# pca10095_sheet3_interface_mcu.net
KiCad netlist of a schematic drawn in Altium Designer
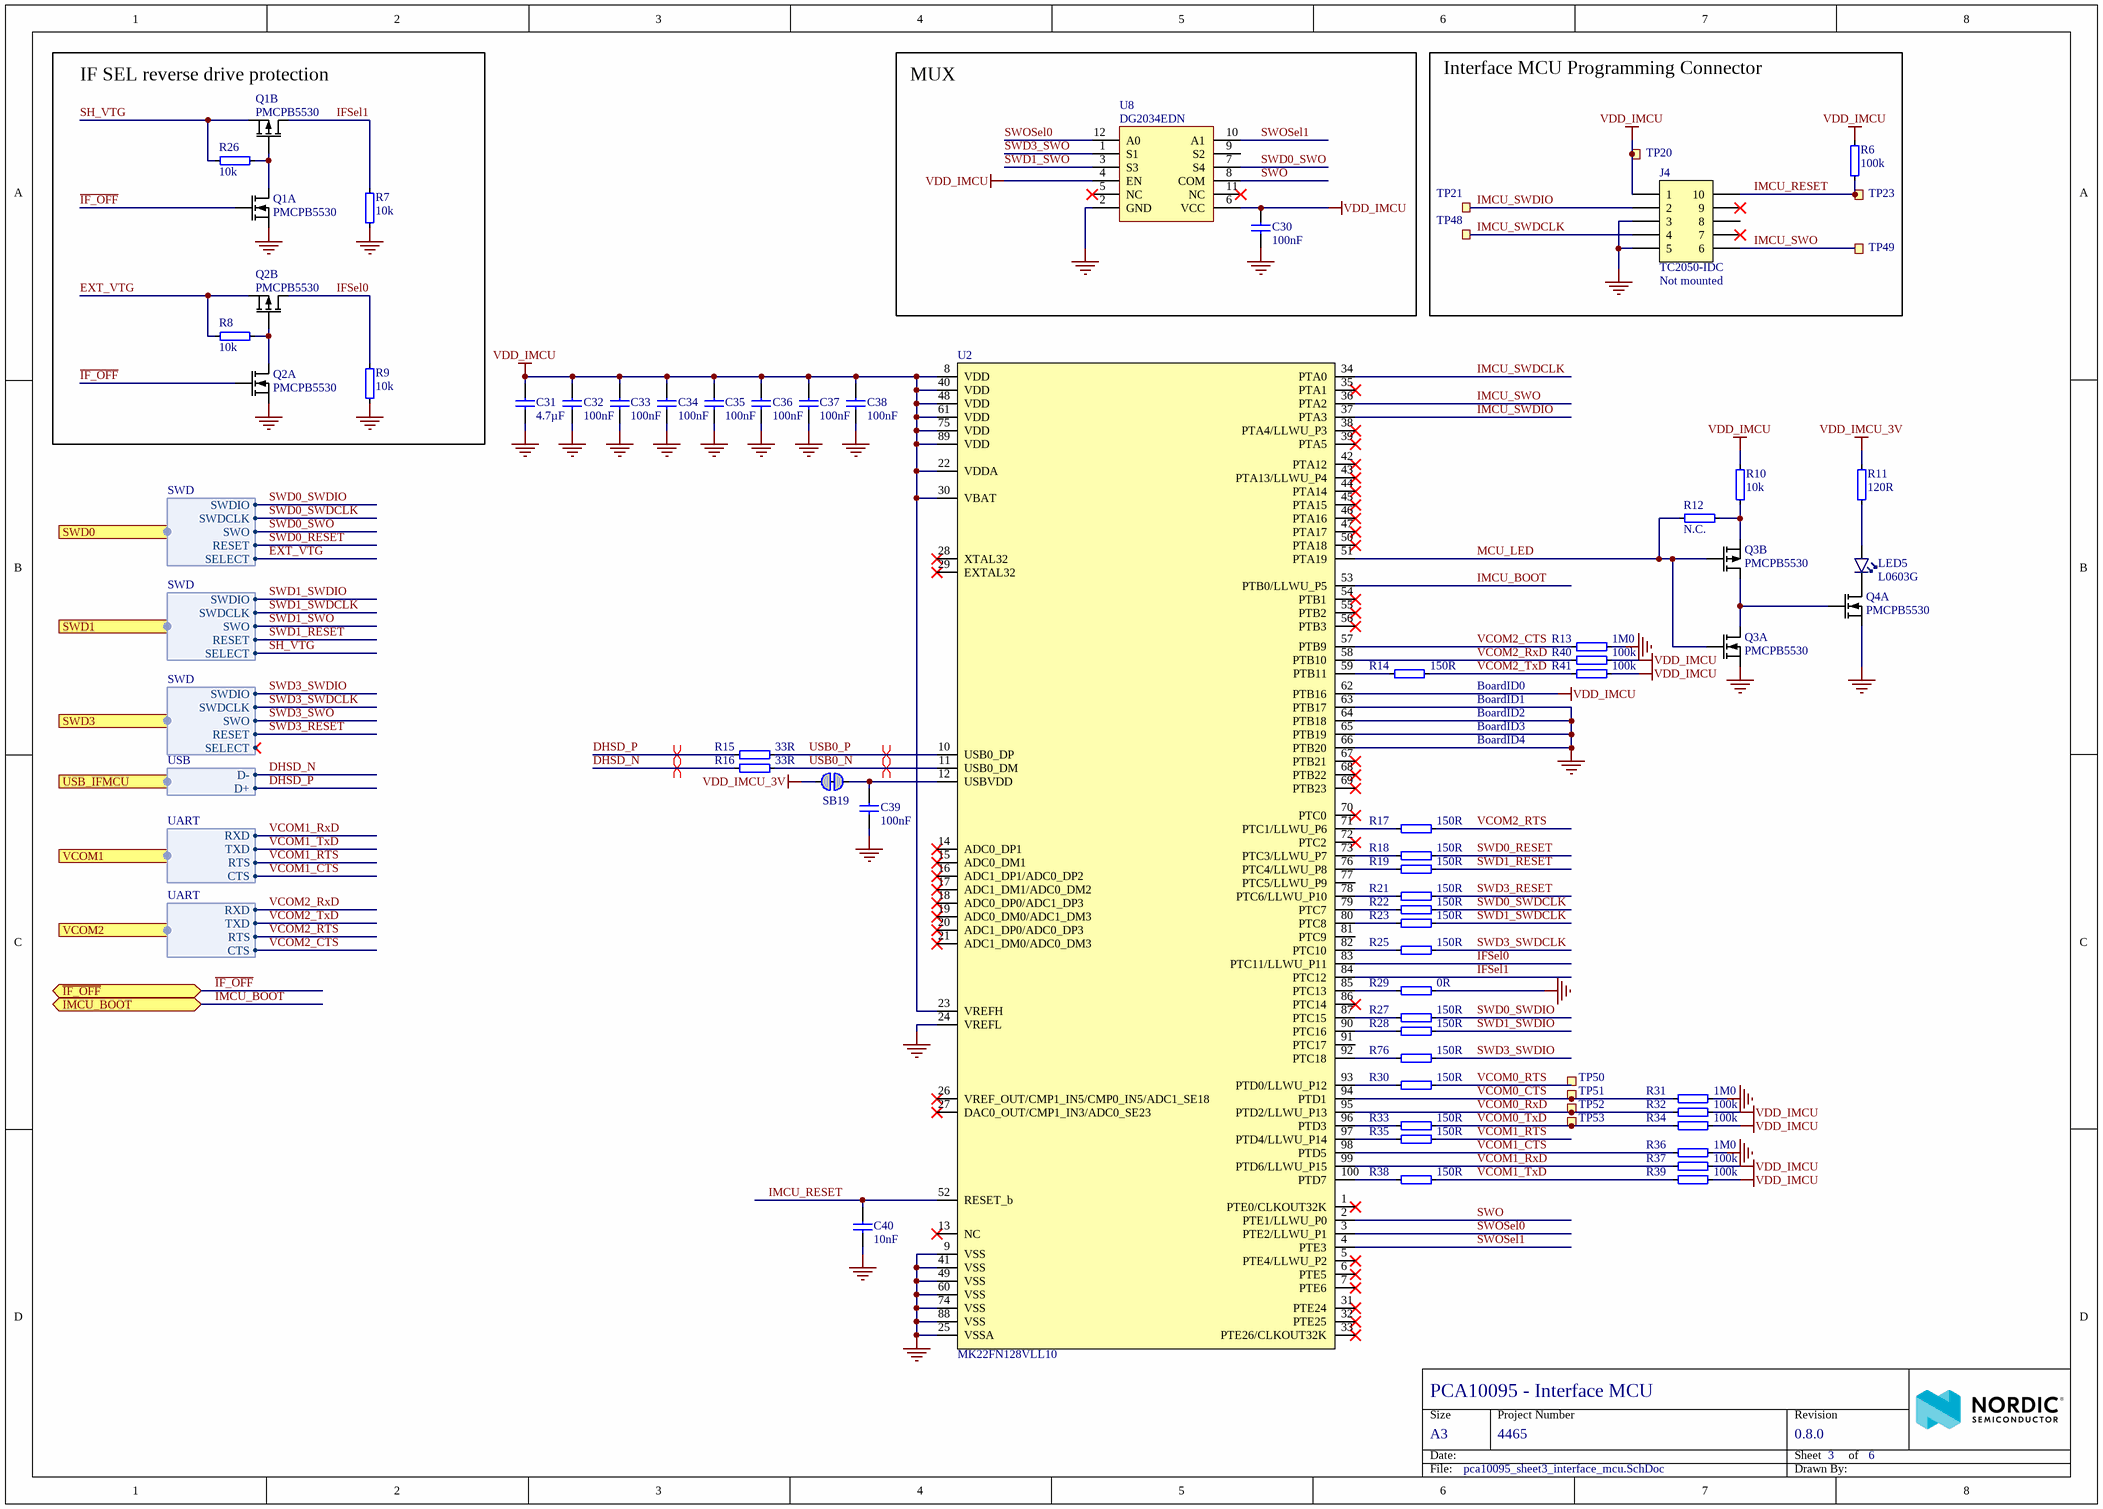
[diagram p0: pca10095_sheet3_interface_mcu.SchDoc]

(export (version "E")
  (design (tool "Eeschema 10.0.6"))
  (components
    (comp (ref "C30")
      (value "100nF")
      (footprint "CAPC0603X03L_C")
      (description "Capacitor, X5R, ±10%")
      (fields (field (name "PART NUMBER") "C0201-100n") (field (name "PUBLISHER") "Nordic Semiconductor"))
      (libsource (lib "Nordic Passive DB") (part "CAP"))
    )
    (comp (ref "C31")
      (value "4.7µF")
      (footprint "CAPC1005X04L")
      (description "CAP CER 4.7UF 10V X5R 0402")
      (fields
        (field (name "PART NUMBER") "C0402-4µ7-10V-X5R")
        (field (name "MANUFACTURER") "Murata")
        (field (name "PUBLISHER") "Nordic Semiconductor")
      )
      (libsource (lib "Nordic Passive DB") (part "CAP"))
    )
    (comp (ref "C32")
      (value "100nF")
      (footprint "CAPC0603X03L_C")
      (description "Capacitor, X5R, ±10%")
      (fields (field (name "PART NUMBER") "C0201-100n") (field (name "PUBLISHER") "Nordic Semiconductor"))
      (libsource (lib "Nordic Passive DB") (part "CAP"))
    )
    (comp (ref "C33")
      (value "100nF")
      (footprint "CAPC0603X03L_C")
      (description "Capacitor, X5R, ±10%")
      (fields (field (name "PART NUMBER") "C0201-100n") (field (name "PUBLISHER") "Nordic Semiconductor"))
      (libsource (lib "Nordic Passive DB") (part "CAP"))
    )
    (comp (ref "C34")
      (value "100nF")
      (footprint "CAPC0603X03L_C")
      (description "Capacitor, X5R, ±10%")
      (fields (field (name "PART NUMBER") "C0201-100n") (field (name "PUBLISHER") "Nordic Semiconductor"))
      (libsource (lib "Nordic Passive DB") (part "CAP"))
    )
    (comp (ref "C35")
      (value "100nF")
      (footprint "CAPC0603X03L_C")
      (description "Capacitor, X5R, ±10%")
      (fields (field (name "PART NUMBER") "C0201-100n") (field (name "PUBLISHER") "Nordic Semiconductor"))
      (libsource (lib "Nordic Passive DB") (part "CAP"))
    )
    (comp (ref "C36")
      (value "100nF")
      (footprint "CAPC0603X03L_C")
      (description "Capacitor, X5R, ±10%")
      (fields (field (name "PART NUMBER") "C0201-100n") (field (name "PUBLISHER") "Nordic Semiconductor"))
      (libsource (lib "Nordic Passive DB") (part "CAP"))
    )
    (comp (ref "C37")
      (value "100nF")
      (footprint "CAPC0603X03L_C")
      (description "Capacitor, X5R, ±10%")
      (fields (field (name "PART NUMBER") "C0201-100n") (field (name "PUBLISHER") "Nordic Semiconductor"))
      (libsource (lib "Nordic Passive DB") (part "CAP"))
    )
    (comp (ref "C38")
      (value "100nF")
      (footprint "CAPC0603X03L_C")
      (description "Capacitor, X5R, ±10%")
      (fields (field (name "PART NUMBER") "C0201-100n") (field (name "PUBLISHER") "Nordic Semiconductor"))
      (libsource (lib "Nordic Passive DB") (part "CAP"))
    )
    (comp (ref "C39")
      (value "100nF")
      (footprint "CAPC0603X03L_C")
      (description "Capacitor, X5R, ±10%")
      (fields (field (name "PART NUMBER") "C0201-100n") (field (name "PUBLISHER") "Nordic Semiconductor"))
      (libsource (lib "Nordic Passive DB") (part "CAP"))
    )
    (comp (ref "C40")
      (value "10nF")
      (footprint "CAPC0603X03L_C")
      (description "Capacitor, X7R, ±10%")
      (fields (field (name "PART NUMBER") "C0201-10n") (field (name "PUBLISHER") "Nordic Semiconductor"))
      (libsource (lib "Nordic Passive DB") (part "CAP"))
    )
    (comp (ref "J4")
      (value "TC2050-IDC")
      (footprint "TC2050-IDC-NLFP")
      (description "CBL PLUG-OF-NAILS 10-PIN")
      (fields
        (field (name "PART NUMBER") "TC2050-IDC-NLFP")
        (field (name "MANUFACTURER") "Tag-Connect LLC")
        (field (name "ASSEMBLY") "Not mounted")
        (field (name "PUBLISHER") "Nordic Semiconductor")
      )
      (libsource (lib "Nordic Passive DB") (part "CONN-2x5_var2_No_BOM"))
    )
    (comp (ref "LED5")
      (value "L0603G")
      (footprint "LED_0603_G")
      (description "LED, Green, 0603, 570nm, Vf=1.7V, 2.24..5.6mcd, - 40 to +100°C")
      (fields
        (field (name "PART NUMBER") "LG L29K Smartled Green")
        (field (name "MANUFACTURER") "Osram")
        (field (name "PUBLISHER") "Nordic Semiconductor")
      )
      (libsource (lib "Nordic Discrete DB") (part "D{colon}LED"))
    )
    (comp (ref "Q1")
      (value "PMCPB5530")
      (footprint "PMCPB5530X")
      (description "Mosfet Array N and P-Channel 20V 4A (Ta), 3.4A (Ta) 490mW Surface Mount 6-HUSON-EP (2x2)")
      (fields
        (field (name "PART NUMBER") "PMCPB5530X,115")
        (field (name "MANUFACTURER") "Nexperia")
        (field (name "PUBLISHER") "Nordic Semiconductor")
      )
      (libsource (lib "Nordic Discrete DB") (part "T{colon}FET-N/P-DUAL"))
    )
    (comp (ref "Q2")
      (value "PMCPB5530")
      (footprint "PMCPB5530X")
      (description "Mosfet Array N and P-Channel 20V 4A (Ta), 3.4A (Ta) 490mW Surface Mount 6-HUSON-EP (2x2)")
      (fields
        (field (name "PART NUMBER") "PMCPB5530X,115")
        (field (name "MANUFACTURER") "Nexperia")
        (field (name "PUBLISHER") "Nordic Semiconductor")
      )
      (libsource (lib "Nordic Discrete DB") (part "T{colon}FET-N/P-DUAL"))
    )
    (comp (ref "Q3")
      (value "PMCPB5530")
      (footprint "PMCPB5530X")
      (description "Mosfet Array N and P-Channel 20V 4A (Ta), 3.4A (Ta) 490mW Surface Mount 6-HUSON-EP (2x2)")
      (fields
        (field (name "PART NUMBER") "PMCPB5530X,115")
        (field (name "MANUFACTURER") "Nexperia")
        (field (name "PUBLISHER") "Nordic Semiconductor")
      )
      (libsource (lib "Nordic Discrete DB") (part "T{colon}FET-N/P-DUAL"))
    )
    (comp (ref "Q4")
      (value "PMCPB5530")
      (footprint "PMCPB5530X")
      (description "Mosfet Array N and P-Channel 20V 4A (Ta), 3.4A (Ta) 490mW Surface Mount 6-HUSON-EP (2x2)")
      (fields
        (field (name "PART NUMBER") "PMCPB5530X,115")
        (field (name "MANUFACTURER") "Nexperia")
        (field (name "PUBLISHER") "Nordic Semiconductor")
      )
      (libsource (lib "Nordic Discrete DB") (part "T{colon}FET-N/P-DUAL"))
    )
    (comp (ref "R6")
      (value "100k")
      (footprint "RESC0603X03L_C")
      (description "Resistor, ±1%, 0.05W")
      (fields (field (name "PART NUMBER") "R0201-100k") (field (name "PUBLISHER") "Nordic Semiconductor"))
      (libsource (lib "Nordic Passive DB") (part "RES_1"))
    )
    (comp (ref "R7")
      (value "10k")
      (footprint "RESC0603X03L_C")
      (description "Resistor, ±1%, 0.05W")
      (fields (field (name "PART NUMBER") "R0201-10k") (field (name "PUBLISHER") "Nordic Semiconductor"))
      (libsource (lib "Nordic Passive DB") (part "RES_1"))
    )
    (comp (ref "R8")
      (value "10k")
      (footprint "RESC0603X03L_C")
      (description "Resistor, ±1%, 0.05W")
      (fields (field (name "PART NUMBER") "R0201-10k") (field (name "PUBLISHER") "Nordic Semiconductor"))
      (libsource (lib "Nordic Passive DB") (part "RES_1"))
    )
    (comp (ref "R9")
      (value "10k")
      (footprint "RESC0603X03L_C")
      (description "Resistor, ±1%, 0.05W")
      (fields (field (name "PART NUMBER") "R0201-10k") (field (name "PUBLISHER") "Nordic Semiconductor"))
      (libsource (lib "Nordic Passive DB") (part "RES_1"))
    )
    (comp (ref "R10")
      (value "10k")
      (footprint "RESC0603X03L_C")
      (description "Resistor, ±1%, 0.05W")
      (fields (field (name "PART NUMBER") "R0201-10k") (field (name "PUBLISHER") "Nordic Semiconductor"))
      (libsource (lib "Nordic Passive DB") (part "RES_1"))
    )
    (comp (ref "R11")
      (value "120R")
      (footprint "RESC0603X03L_C")
      (description "Resistor, ±1%, 0.05W")
      (fields (field (name "PART NUMBER") "R0201-120") (field (name "PUBLISHER") "Nordic Semiconductor"))
      (libsource (lib "Nordic Passive DB") (part "RES_1"))
    )
    (comp (ref "R12")
      (value "N.C.")
      (footprint "RESC0603X03L_C")
      (description "Not mounted")
      (fields (field (name "PART NUMBER") "R0201-N.C.") (field (name "PUBLISHER") "Nordic Semiconductor"))
      (libsource (lib "Nordic Passive DB") (part "RES_1"))
    )
    (comp (ref "R13")
      (value "1M0")
      (footprint "RESC0603X03L_C")
      (description "Resistor, ±1%, 0.05W")
      (fields (field (name "PART NUMBER") "R0201-1M0") (field (name "PUBLISHER") "Nordic Semiconductor"))
      (libsource (lib "Nordic Passive DB") (part "RES_1"))
    )
    (comp (ref "R14")
      (value "150R")
      (footprint "RESC0603X03L_C")
      (description "Resistor, ±1%, 0.05W")
      (fields (field (name "PART NUMBER") "R0201-150") (field (name "PUBLISHER") "Nordic Semiconductor"))
      (libsource (lib "Nordic Passive DB") (part "RES_1"))
    )
    (comp (ref "R15")
      (value "33R")
      (footprint "RESC0603X03L_C")
      (description "Resistor, ±1%, 0.05W")
      (fields (field (name "PART NUMBER") "R0201-33R") (field (name "PUBLISHER") "Nordic Semiconductor"))
      (libsource (lib "Nordic Passive DB") (part "RES_1"))
    )
    (comp (ref "R16")
      (value "33R")
      (footprint "RESC0603X03L_C")
      (description "Resistor, ±1%, 0.05W")
      (fields (field (name "PART NUMBER") "R0201-33R") (field (name "PUBLISHER") "Nordic Semiconductor"))
      (libsource (lib "Nordic Passive DB") (part "RES_1"))
    )
    (comp (ref "R17")
      (value "150R")
      (footprint "RESC0603X03L_C")
      (description "Resistor, ±1%, 0.05W")
      (fields (field (name "PART NUMBER") "R0201-150") (field (name "PUBLISHER") "Nordic Semiconductor"))
      (libsource (lib "Nordic Passive DB") (part "RES_1"))
    )
    (comp (ref "R18")
      (value "150R")
      (footprint "RESC0603X03L_C")
      (description "Resistor, ±1%, 0.05W")
      (fields (field (name "PART NUMBER") "R0201-150") (field (name "PUBLISHER") "Nordic Semiconductor"))
      (libsource (lib "Nordic Passive DB") (part "RES_1"))
    )
    (comp (ref "R19")
      (value "150R")
      (footprint "RESC0603X03L_C")
      (description "Resistor, ±1%, 0.05W")
      (fields (field (name "PART NUMBER") "R0201-150") (field (name "PUBLISHER") "Nordic Semiconductor"))
      (libsource (lib "Nordic Passive DB") (part "RES_1"))
    )
    (comp (ref "R21")
      (value "150R")
      (footprint "RESC0603X03L_C")
      (description "Resistor, ±1%, 0.05W")
      (fields (field (name "PART NUMBER") "R0201-150") (field (name "PUBLISHER") "Nordic Semiconductor"))
      (libsource (lib "Nordic Passive DB") (part "RES_1"))
    )
    (comp (ref "R22")
      (value "150R")
      (footprint "RESC0603X03L_C")
      (description "Resistor, ±1%, 0.05W")
      (fields (field (name "PART NUMBER") "R0201-150") (field (name "PUBLISHER") "Nordic Semiconductor"))
      (libsource (lib "Nordic Passive DB") (part "RES_1"))
    )
    (comp (ref "R23")
      (value "150R")
      (footprint "RESC0603X03L_C")
      (description "Resistor, ±1%, 0.05W")
      (fields (field (name "PART NUMBER") "R0201-150") (field (name "PUBLISHER") "Nordic Semiconductor"))
      (libsource (lib "Nordic Passive DB") (part "RES_1"))
    )
    (comp (ref "R25")
      (value "150R")
      (footprint "RESC0603X03L_C")
      (description "Resistor, ±1%, 0.05W")
      (fields (field (name "PART NUMBER") "R0201-150") (field (name "PUBLISHER") "Nordic Semiconductor"))
      (libsource (lib "Nordic Passive DB") (part "RES_1"))
    )
    (comp (ref "R26")
      (value "10k")
      (footprint "RESC0603X03L_C")
      (description "Resistor, ±1%, 0.05W")
      (fields (field (name "PART NUMBER") "R0201-10k") (field (name "PUBLISHER") "Nordic Semiconductor"))
      (libsource (lib "Nordic Passive DB") (part "RES_1"))
    )
    (comp (ref "R27")
      (value "150R")
      (footprint "RESC0603X03L_C")
      (description "Resistor, ±1%, 0.05W")
      (fields (field (name "PART NUMBER") "R0201-150") (field (name "PUBLISHER") "Nordic Semiconductor"))
      (libsource (lib "Nordic Passive DB") (part "RES_1"))
    )
    (comp (ref "R28")
      (value "150R")
      (footprint "RESC0603X03L_C")
      (description "Resistor, ±1%, 0.05W")
      (fields (field (name "PART NUMBER") "R0201-150") (field (name "PUBLISHER") "Nordic Semiconductor"))
      (libsource (lib "Nordic Passive DB") (part "RES_1"))
    )
    (comp (ref "R29")
      (value "0R")
      (footprint "RESC0603X03L_C")
      (description "Resistor, ±5%, 0.05W")
      (fields (field (name "PART NUMBER") "R0201-0R") (field (name "PUBLISHER") "Nordic Semiconductor"))
      (libsource (lib "Nordic Passive DB") (part "RES_1"))
    )
    (comp (ref "R30")
      (value "150R")
      (footprint "RESC0603X03L_C")
      (description "Resistor, ±1%, 0.05W")
      (fields (field (name "PART NUMBER") "R0201-150") (field (name "PUBLISHER") "Nordic Semiconductor"))
      (libsource (lib "Nordic Passive DB") (part "RES_1"))
    )
    (comp (ref "R31")
      (value "1M0")
      (footprint "RESC0603X03L_C")
      (description "Resistor, ±1%, 0.05W")
      (fields (field (name "PART NUMBER") "R0201-1M0") (field (name "PUBLISHER") "Nordic Semiconductor"))
      (libsource (lib "Nordic Passive DB") (part "RES_1"))
    )
    (comp (ref "R32")
      (value "100k")
      (footprint "RESC0603X03L_C")
      (description "Resistor, ±1%, 0.05W")
      (fields (field (name "PART NUMBER") "R0201-100k") (field (name "PUBLISHER") "Nordic Semiconductor"))
      (libsource (lib "Nordic Passive DB") (part "RES_1"))
    )
    (comp (ref "R33")
      (value "150R")
      (footprint "RESC0603X03L_C")
      (description "Resistor, ±1%, 0.05W")
      (fields (field (name "PART NUMBER") "R0201-150") (field (name "PUBLISHER") "Nordic Semiconductor"))
      (libsource (lib "Nordic Passive DB") (part "RES_1"))
    )
    (comp (ref "R34")
      (value "100k")
      (footprint "RESC0603X03L_C")
      (description "Resistor, ±1%, 0.05W")
      (fields (field (name "PART NUMBER") "R0201-100k") (field (name "PUBLISHER") "Nordic Semiconductor"))
      (libsource (lib "Nordic Passive DB") (part "RES_1"))
    )
    (comp (ref "R35")
      (value "150R")
      (footprint "RESC0603X03L_C")
      (description "Resistor, ±1%, 0.05W")
      (fields (field (name "PART NUMBER") "R0201-150") (field (name "PUBLISHER") "Nordic Semiconductor"))
      (libsource (lib "Nordic Passive DB") (part "RES_1"))
    )
    (comp (ref "R36")
      (value "1M0")
      (footprint "RESC0603X03L_C")
      (description "Resistor, ±1%, 0.05W")
      (fields (field (name "PART NUMBER") "R0201-1M0") (field (name "PUBLISHER") "Nordic Semiconductor"))
      (libsource (lib "Nordic Passive DB") (part "RES_1"))
    )
    (comp (ref "R37")
      (value "100k")
      (footprint "RESC0603X03L_C")
      (description "Resistor, ±1%, 0.05W")
      (fields (field (name "PART NUMBER") "R0201-100k") (field (name "PUBLISHER") "Nordic Semiconductor"))
      (libsource (lib "Nordic Passive DB") (part "RES_1"))
    )
    (comp (ref "R38")
      (value "150R")
      (footprint "RESC0603X03L_C")
      (description "Resistor, ±1%, 0.05W")
      (fields (field (name "PART NUMBER") "R0201-150") (field (name "PUBLISHER") "Nordic Semiconductor"))
      (libsource (lib "Nordic Passive DB") (part "RES_1"))
    )
    (comp (ref "R39")
      (value "100k")
      (footprint "RESC0603X03L_C")
      (description "Resistor, ±1%, 0.05W")
      (fields (field (name "PART NUMBER") "R0201-100k") (field (name "PUBLISHER") "Nordic Semiconductor"))
      (libsource (lib "Nordic Passive DB") (part "RES_1"))
    )
    (comp (ref "R40")
      (value "100k")
      (footprint "RESC0603X03L_C")
      (description "Resistor, ±1%, 0.05W")
      (fields (field (name "PART NUMBER") "R0201-100k") (field (name "PUBLISHER") "Nordic Semiconductor"))
      (libsource (lib "Nordic Passive DB") (part "RES_1"))
    )
    (comp (ref "R41")
      (value "100k")
      (footprint "RESC0603X03L_C")
      (description "Resistor, ±1%, 0.05W")
      (fields (field (name "PART NUMBER") "R0201-100k") (field (name "PUBLISHER") "Nordic Semiconductor"))
      (libsource (lib "Nordic Passive DB") (part "RES_1"))
    )
    (comp (ref "R76")
      (value "150R")
      (footprint "RESC0603X03L_C")
      (description "Resistor, ±1%, 0.05W")
      (fields (field (name "PART NUMBER") "R0201-150") (field (name "PUBLISHER") "Nordic Semiconductor"))
      (libsource (lib "Nordic Passive DB") (part "RES_1"))
    )
    (comp (ref "SB19")
      (value "Solderbridge")
      (footprint "Solderbridge_Shorted")
      (description "Shorted Solderbridge")
      (fields
        (field (name "PART NUMBER") "Solderbridge Shorted")
        (field (name "PUBLISHER") "Nordic Semiconductor")
      )
      (libsource (lib "Nordic Passive DB") (part "SOLDERBRIDGE_SHORTED"))
    )
    (comp (ref "TP20")
      (value "Ø1.5mm,SMD")
      (footprint "TP_SMD_Ø1.5mm")
      (description "1.0mm circular SMD testpad")
      (fields
        (field (name "PART NUMBER") "TP_SMD_Ø1.5MM")
        (field (name "MANUFACTURER") "Nordic Semiconductor")
        (field (name "PUBLISHER") "Nordic Semiconductor")
      )
      (libsource (lib "") (part "TESTPAD_1"))
    )
    (comp (ref "TP21")
      (value "Ø1.5mm,SMD")
      (footprint "TP_SMD_Ø1.5mm")
      (description "1.0mm circular SMD testpad")
      (fields
        (field (name "PART NUMBER") "TP_SMD_Ø1.5MM")
        (field (name "MANUFACTURER") "Nordic Semiconductor")
        (field (name "PUBLISHER") "Nordic Semiconductor")
      )
      (libsource (lib "Nordic Passive DB") (part "TESTPAD"))
    )
    (comp (ref "TP23")
      (value "Ø1.5mm,SMD")
      (footprint "TP_SMD_Ø1.5mm")
      (description "1.0mm circular SMD testpad")
      (fields
        (field (name "PART NUMBER") "TP_SMD_Ø1.5MM")
        (field (name "MANUFACTURER") "Nordic Semiconductor")
        (field (name "PUBLISHER") "Nordic Semiconductor")
      )
      (libsource (lib "") (part "TESTPAD_1"))
    )
    (comp (ref "TP48")
      (value "Ø1.5mm,SMD")
      (footprint "TP_SMD_Ø1.5mm")
      (description "1.0mm circular SMD testpad")
      (fields
        (field (name "PART NUMBER") "TP_SMD_Ø1.5MM")
        (field (name "MANUFACTURER") "Nordic Semiconductor")
        (field (name "PUBLISHER") "Nordic Semiconductor")
      )
      (libsource (lib "Nordic Passive DB") (part "TESTPAD"))
    )
    (comp (ref "TP49")
      (value "Ø1.5mm,SMD")
      (footprint "TP_SMD_Ø1.5mm")
      (description "1.0mm circular SMD testpad")
      (fields
        (field (name "PART NUMBER") "TP_SMD_Ø1.5MM")
        (field (name "MANUFACTURER") "Nordic Semiconductor")
        (field (name "PUBLISHER") "Nordic Semiconductor")
      )
      (libsource (lib "") (part "TESTPAD_1"))
    )
    (comp (ref "TP50")
      (value "Ø1.0mm,SMD")
      (footprint "TP_SMD_Ø1.0mm")
      (description "1.0mm circular SMD testpad")
      (fields
        (field (name "PART NUMBER") "TP_SMD_Ø1.0MM")
        (field (name "MANUFACTURER") "Nordic Semiconductor")
        (field (name "PUBLISHER") "Nordic Semiconductor")
      )
      (libsource (lib "") (part "TESTPAD_2"))
    )
    (comp (ref "TP51")
      (value "Ø1.0mm,SMD")
      (footprint "TP_SMD_Ø1.0mm")
      (description "1.0mm circular SMD testpad")
      (fields
        (field (name "PART NUMBER") "TP_SMD_Ø1.0MM")
        (field (name "MANUFACTURER") "Nordic Semiconductor")
        (field (name "PUBLISHER") "Nordic Semiconductor")
      )
      (libsource (lib "") (part "TESTPAD_2"))
    )
    (comp (ref "TP52")
      (value "Ø1.0mm,SMD")
      (footprint "TP_SMD_Ø1.0mm")
      (description "1.0mm circular SMD testpad")
      (fields
        (field (name "PART NUMBER") "TP_SMD_Ø1.0MM")
        (field (name "MANUFACTURER") "Nordic Semiconductor")
        (field (name "PUBLISHER") "Nordic Semiconductor")
      )
      (libsource (lib "") (part "TESTPAD_2"))
    )
    (comp (ref "TP53")
      (value "Ø1.0mm,SMD")
      (footprint "TP_SMD_Ø1.0mm")
      (description "1.0mm circular SMD testpad")
      (fields
        (field (name "PART NUMBER") "TP_SMD_Ø1.0MM")
        (field (name "MANUFACTURER") "Nordic Semiconductor")
        (field (name "PUBLISHER") "Nordic Semiconductor")
      )
      (libsource (lib "") (part "TESTPAD_2"))
    )
    (comp (ref "U2")
      (value "MK22FN128VLL10")
      (footprint "TSQFP50P1600X1600X160-100N")
      (description "100MHz Cortex-M4F Performance MCU, 128kB Flash, 24kB SRAM, Full-Speed USB")
      (fields (field (name "MANUFACTURER") "NXP") (field (name "PUBLISHER") "Nordic Semiconductor"))
      (libsource (lib "Nordic Active DB") (part "MK22FN128VLL10"))
    )
    (comp (ref "U8")
      (value "DG2034EDN")
      (footprint "DG2034EDN")
      (description "POWER DOWN FAULT PROTECTED,1.8VT")
      (fields
        (field (name "MANUFACTURER") "Vishay Siliconix")
        (field (name "MANUFACTURER PART NUMBER") "DG2034EDN-T1-GE4")
        (field (name "PUBLISHER") "Nordic Semiconductor")
      )
      (libsource (lib "Nordic Active DB") (part "DG2034EDN"))
    )
  )
  (nets
    (net (code "4") (name "/DHSD_N") (class "Default")
      (node (ref "R16") (pin "1") (pinfunction "1_1") (pintype "passive"))
    )
    (net (code "5") (name "/DHSD_P") (class "Default")
      (node (ref "R15") (pin "1") (pinfunction "1_1") (pintype "passive"))
    )
    (net (code "6") (name "/EXT_VTG") (class "Default")
      (node (ref "Q2") (pin "4") (pinfunction "S2_4") (pintype "passive"))
      (node (ref "R8") (pin "1") (pinfunction "1_1") (pintype "passive"))
    )
    (net (code "7") (name "/IFSel0") (class "Default")
      (node (ref "Q2") (pin "3") (pinfunction "D2_3") (pintype "passive"))
      (node (ref "R9") (pin "2") (pinfunction "2_2") (pintype "passive"))
      (node (ref "U2") (pin "83") (pinfunction "PTC11/LLWU_P11_83") (pintype "passive"))
    )
    (net (code "8") (name "/IFSel1") (class "Default")
      (node (ref "Q1") (pin "3") (pinfunction "D2_3") (pintype "passive"))
      (node (ref "R7") (pin "2") (pinfunction "2_2") (pintype "passive"))
      (node (ref "U2") (pin "84") (pinfunction "PTC12_84") (pintype "passive"))
    )
    (net (code "9") (name "/IMCU_BOOT") (class "Default")
      (node (ref "U2") (pin "53") (pinfunction "PTB0/LLWU_P5_53") (pintype "passive"))
    )
    (net (code "10") (name "/IMCU_RESET") (class "Default")
      (node (ref "C40") (pin "2") (pinfunction "2_2") (pintype "passive"))
      (node (ref "J4") (pin "10") (pinfunction "10_10") (pintype "passive"))
      (node (ref "R6") (pin "1") (pinfunction "1_1") (pintype "passive"))
      (node (ref "TP23") (pin "1") (pinfunction "1_1") (pintype "passive"))
      (node (ref "U2") (pin "52") (pinfunction "RESET_b_52") (pintype "passive"))
    )
    (net (code "11") (name "/IMCU_SWDCLK") (class "Default")
      (node (ref "J4") (pin "4") (pinfunction "4_4") (pintype "passive"))
      (node (ref "TP48") (pin "1") (pinfunction "1_1") (pintype "passive"))
      (node (ref "U2") (pin "34") (pinfunction "PTA0_34") (pintype "passive"))
    )
    (net (code "12") (name "/IMCU_SWDIO") (class "Default")
      (node (ref "J4") (pin "2") (pinfunction "2_2") (pintype "passive"))
      (node (ref "TP21") (pin "1") (pinfunction "1_1") (pintype "passive"))
      (node (ref "U2") (pin "37") (pinfunction "PTA3_37") (pintype "passive"))
    )
    (net (code "13") (name "/IMCU_SWO") (class "Default")
      (node (ref "J4") (pin "6") (pinfunction "6_6") (pintype "passive"))
      (node (ref "TP49") (pin "1") (pinfunction "1_1") (pintype "passive"))
      (node (ref "U2") (pin "36") (pinfunction "PTA2_36") (pintype "passive"))
    )
    (net (code "14") (name "/MCU_LED") (class "Default")
      (node (ref "Q3") (pin "2") (pinfunction "G1_2") (pintype "passive"))
      (node (ref "Q3") (pin "5") (pinfunction "G2_5") (pintype "passive"))
      (node (ref "R12") (pin "1") (pinfunction "1_1") (pintype "passive"))
      (node (ref "U2") (pin "51") (pinfunction "PTA19_51") (pintype "passive"))
    )
    (net (code "15") (name "/SH_VTG") (class "Default")
      (node (ref "Q1") (pin "4") (pinfunction "S2_4") (pintype "passive"))
      (node (ref "R26") (pin "1") (pinfunction "1_1") (pintype "passive"))
    )
    (net (code "16") (name "/SWD0_RESET") (class "Default")
      (node (ref "R18") (pin "2") (pinfunction "2_2") (pintype "passive"))
    )
    (net (code "17") (name "/SWD0_SWDCLK") (class "Default")
      (node (ref "R22") (pin "2") (pinfunction "2_2") (pintype "passive"))
    )
    (net (code "18") (name "/SWD0_SWDIO") (class "Default")
      (node (ref "R27") (pin "2") (pinfunction "2_2") (pintype "passive"))
    )
    (net (code "19") (name "/SWD0_SWO") (class "Default")
      (node (ref "U8") (pin "7") (pinfunction "S4_7") (pintype "passive"))
    )
    (net (code "20") (name "/SWD1_RESET") (class "Default")
      (node (ref "R19") (pin "2") (pinfunction "2_2") (pintype "passive"))
    )
    (net (code "21") (name "/SWD1_SWDCLK") (class "Default")
      (node (ref "R23") (pin "2") (pinfunction "2_2") (pintype "passive"))
    )
    (net (code "22") (name "/SWD1_SWDIO") (class "Default")
      (node (ref "R28") (pin "2") (pinfunction "2_2") (pintype "passive"))
    )
    (net (code "23") (name "/SWD1_SWO") (class "Default")
      (node (ref "U8") (pin "3") (pinfunction "S3_3") (pintype "power_in"))
    )
    (net (code "24") (name "/SWD3_RESET") (class "Default")
      (node (ref "R21") (pin "2") (pinfunction "2_2") (pintype "passive"))
    )
    (net (code "25") (name "/SWD3_SWDCLK") (class "Default")
      (node (ref "R25") (pin "2") (pinfunction "2_2") (pintype "passive"))
    )
    (net (code "26") (name "/SWD3_SWDIO") (class "Default")
      (node (ref "R76") (pin "2") (pinfunction "2_2") (pintype "passive"))
    )
    (net (code "27") (name "/SWD3_SWO") (class "Default")
      (node (ref "U8") (pin "1") (pinfunction "S1_1") (pintype "passive"))
    )
    (net (code "28") (name "/SWO") (class "Default")
      (node (ref "U2") (pin "2") (pinfunction "PTE1/LLWU_P0_2") (pintype "passive"))
      (node (ref "U8") (pin "8") (pinfunction "COM_8") (pintype "passive"))
    )
    (net (code "29") (name "/SWOSel0") (class "Default")
      (node (ref "U2") (pin "3") (pinfunction "PTE2/LLWU_P1_3") (pintype "passive"))
      (node (ref "U8") (pin "12") (pinfunction "A0_12") (pintype "passive"))
    )
    (net (code "30") (name "/SWOSel1") (class "Default")
      (node (ref "U2") (pin "4") (pinfunction "PTE3_4") (pintype "passive"))
      (node (ref "U8") (pin "10") (pinfunction "A1_10") (pintype "passive"))
    )
    (net (code "31") (name "/USB0_N") (class "Default")
      (node (ref "R16") (pin "2") (pinfunction "2_2") (pintype "passive"))
      (node (ref "U2") (pin "11") (pinfunction "USB0_DM_11") (pintype "passive"))
    )
    (net (code "32") (name "/USB0_P") (class "Default")
      (node (ref "R15") (pin "2") (pinfunction "2_2") (pintype "passive"))
      (node (ref "U2") (pin "10") (pinfunction "USB0_DP_10") (pintype "passive"))
    )
    (net (code "33") (name "/VCOM0_CTS") (class "Default")
      (node (ref "R31") (pin "1") (pinfunction "1_1") (pintype "passive"))
      (node (ref "TP51") (pin "1") (pinfunction "1_1") (pintype "passive"))
      (node (ref "U2") (pin "94") (pinfunction "PTD1_94") (pintype "passive"))
    )
    (net (code "34") (name "/VCOM0_RTS") (class "Default")
      (node (ref "R30") (pin "2") (pinfunction "2_2") (pintype "passive"))
      (node (ref "TP50") (pin "1") (pinfunction "1_1") (pintype "passive"))
    )
    (net (code "35") (name "/VCOM0_RxD") (class "Default")
      (node (ref "R32") (pin "1") (pinfunction "1_1") (pintype "passive"))
      (node (ref "TP52") (pin "1") (pinfunction "1_1") (pintype "passive"))
      (node (ref "U2") (pin "95") (pinfunction "PTD2/LLWU_P13_95") (pintype "passive"))
    )
    (net (code "36") (name "/VCOM0_TxD") (class "Default")
      (node (ref "R33") (pin "2") (pinfunction "2_2") (pintype "passive"))
      (node (ref "R34") (pin "1") (pinfunction "1_1") (pintype "passive"))
      (node (ref "TP53") (pin "1") (pinfunction "1_1") (pintype "passive"))
    )
    (net (code "37") (name "/VCOM1_CTS") (class "Default")
      (node (ref "R36") (pin "1") (pinfunction "1_1") (pintype "passive"))
      (node (ref "U2") (pin "98") (pinfunction "PTD5_98") (pintype "passive"))
    )
    (net (code "38") (name "/VCOM1_RTS") (class "Default")
      (node (ref "R35") (pin "2") (pinfunction "2_2") (pintype "passive"))
    )
    (net (code "39") (name "/VCOM1_RxD") (class "Default")
      (node (ref "R37") (pin "1") (pinfunction "1_1") (pintype "passive"))
      (node (ref "U2") (pin "99") (pinfunction "PTD6/LLWU_P15_99") (pintype "passive"))
    )
    (net (code "40") (name "/VCOM1_TxD") (class "Default")
      (node (ref "R38") (pin "2") (pinfunction "2_2") (pintype "passive"))
      (node (ref "R39") (pin "1") (pinfunction "1_1") (pintype "passive"))
    )
    (net (code "41") (name "/VCOM2_CTS") (class "Default")
      (node (ref "R13") (pin "1") (pinfunction "1_1") (pintype "passive"))
      (node (ref "U2") (pin "57") (pinfunction "PTB9_57") (pintype "passive"))
    )
    (net (code "42") (name "/VCOM2_RTS") (class "Default")
      (node (ref "R17") (pin "2") (pinfunction "2_2") (pintype "passive"))
    )
    (net (code "43") (name "/VCOM2_RxD") (class "Default")
      (node (ref "R40") (pin "1") (pinfunction "1_1") (pintype "passive"))
      (node (ref "U2") (pin "58") (pinfunction "PTB10_58") (pintype "passive"))
    )
    (net (code "44") (name "/VCOM2_TxD") (class "Default")
      (node (ref "R14") (pin "2") (pinfunction "2_2") (pintype "passive"))
      (node (ref "R41") (pin "1") (pinfunction "1_1") (pintype "passive"))
    )
    (net (code "48") (name "/~{IF_OFF}") (class "Default")
      (node (ref "Q1") (pin "2") (pinfunction "G1_2") (pintype "passive"))
      (node (ref "Q2") (pin "2") (pinfunction "G1_2") (pintype "passive"))
    )
    (net (code "49") (name "GND") (class "Default")
      (node (ref "C30") (pin "2") (pinfunction "2_2") (pintype "passive"))
      (node (ref "C31") (pin "1") (pinfunction "1_1") (pintype "passive"))
      (node (ref "C32") (pin "1") (pinfunction "1_1") (pintype "passive"))
      (node (ref "C33") (pin "1") (pinfunction "1_1") (pintype "passive"))
      (node (ref "C34") (pin "2") (pinfunction "2_2") (pintype "passive"))
      (node (ref "C35") (pin "1") (pinfunction "1_1") (pintype "passive"))
      (node (ref "C36") (pin "1") (pinfunction "1_1") (pintype "passive"))
      (node (ref "C37") (pin "1") (pinfunction "1_1") (pintype "passive"))
      (node (ref "C38") (pin "1") (pinfunction "1_1") (pintype "passive"))
      (node (ref "C39") (pin "2") (pinfunction "2_2") (pintype "passive"))
      (node (ref "C40") (pin "1") (pinfunction "1_1") (pintype "passive"))
      (node (ref "J4") (pin "3") (pinfunction "3_3") (pintype "passive"))
      (node (ref "J4") (pin "5") (pinfunction "5_5") (pintype "passive"))
      (node (ref "Q1") (pin "1") (pinfunction "S1_1") (pintype "passive"))
      (node (ref "Q2") (pin "1") (pinfunction "S1_1") (pintype "passive"))
      (node (ref "Q3") (pin "1") (pinfunction "S1_1") (pintype "passive"))
      (node (ref "Q4") (pin "1") (pinfunction "S1_1") (pintype "passive"))
      (node (ref "R13") (pin "2") (pinfunction "2_2") (pintype "passive"))
      (node (ref "R29") (pin "2") (pinfunction "2_2") (pintype "passive"))
      (node (ref "R31") (pin "2") (pinfunction "2_2") (pintype "passive"))
      (node (ref "R36") (pin "2") (pinfunction "2_2") (pintype "passive"))
      (node (ref "R7") (pin "1") (pinfunction "1_1") (pintype "passive"))
      (node (ref "R9") (pin "1") (pinfunction "1_1") (pintype "passive"))
      (node (ref "U2") (pin "24") (pinfunction "VREFL_24") (pintype "passive"))
      (node (ref "U2") (pin "25") (pinfunction "VSSA_25") (pintype "passive"))
      (node (ref "U2") (pin "41") (pinfunction "VSS_41") (pintype "passive"))
      (node (ref "U2") (pin "49") (pinfunction "VSS_49") (pintype "passive"))
      (node (ref "U2") (pin "60") (pinfunction "VSS_60") (pintype "passive"))
      (node (ref "U2") (pin "63") (pinfunction "PTB17_63") (pintype "passive"))
      (node (ref "U2") (pin "64") (pinfunction "PTB18_64") (pintype "passive"))
      (node (ref "U2") (pin "65") (pinfunction "PTB19_65") (pintype "passive"))
      (node (ref "U2") (pin "66") (pinfunction "PTB20_66") (pintype "passive"))
      (node (ref "U2") (pin "74") (pinfunction "VSS_74") (pintype "passive"))
      (node (ref "U2") (pin "88") (pinfunction "VSS_88") (pintype "passive"))
      (node (ref "U2") (pin "9") (pinfunction "VSS_9") (pintype "passive"))
      (node (ref "U8") (pin "2") (pinfunction "GND_2") (pintype "passive"))
    )
    (net (code "50") (name "Net-(LED5-A)") (class "Default")
      (node (ref "LED5") (pin "2") (pinfunction "A_2") (pintype "passive"))
      (node (ref "R11") (pin "1") (pinfunction "1_1") (pintype "passive"))
    )
    (net (code "51") (name "Net-(LED5-C)") (class "Default")
      (node (ref "LED5") (pin "1") (pinfunction "C_1") (pintype "passive"))
      (node (ref "Q4") (pin "6") (pinfunction "D1_6") (pintype "passive"))
    )
    (net (code "52") (name "Net-(Q1A-D1)") (class "Default")
      (node (ref "Q1") (pin "5") (pinfunction "G2_5") (pintype "passive"))
      (node (ref "Q1") (pin "6") (pinfunction "D1_6") (pintype "passive"))
      (node (ref "R26") (pin "2") (pinfunction "2_2") (pintype "passive"))
    )
    (net (code "53") (name "Net-(Q2A-D1)") (class "Default")
      (node (ref "Q2") (pin "5") (pinfunction "G2_5") (pintype "passive"))
      (node (ref "Q2") (pin "6") (pinfunction "D1_6") (pintype "passive"))
      (node (ref "R8") (pin "2") (pinfunction "2_2") (pintype "passive"))
    )
    (net (code "54") (name "Net-(Q3A-D1)") (class "Default")
      (node (ref "Q3") (pin "3") (pinfunction "D2_3") (pintype "passive"))
      (node (ref "Q3") (pin "6") (pinfunction "D1_6") (pintype "passive"))
      (node (ref "Q4") (pin "2") (pinfunction "G1_2") (pintype "passive"))
    )
    (net (code "55") (name "Net-(Q3B-S2)") (class "Default")
      (node (ref "Q3") (pin "4") (pinfunction "S2_4") (pintype "passive"))
      (node (ref "R10") (pin "1") (pinfunction "1_1") (pintype "passive"))
      (node (ref "R12") (pin "2") (pinfunction "2_2") (pintype "passive"))
    )
    (net (code "56") (name "Net-(SB19-0)") (class "Default")
      (node (ref "C39") (pin "1") (pinfunction "1_1") (pintype "passive"))
      (node (ref "SB19") (pin "1") (pinfunction "0_1") (pintype "passive"))
      (node (ref "U2") (pin "12") (pinfunction "USBVDD_12") (pintype "passive"))
    )
    (net (code "57") (name "Net-(U2-PTB11)") (class "Default")
      (node (ref "R14") (pin "1") (pinfunction "1_1") (pintype "passive"))
      (node (ref "U2") (pin "59") (pinfunction "PTB11_59") (pintype "passive"))
    )
    (net (code "58") (name "Net-(U2-PTC1{slash}LLWU_P6)") (class "Default")
      (node (ref "R17") (pin "1") (pinfunction "1_1") (pintype "passive"))
      (node (ref "U2") (pin "71") (pinfunction "PTC1/LLWU_P6_71") (pintype "passive"))
    )
    (net (code "59") (name "Net-(U2-PTC3{slash}LLWU_P7)") (class "Default")
      (node (ref "R18") (pin "1") (pinfunction "1_1") (pintype "passive"))
      (node (ref "U2") (pin "73") (pinfunction "PTC3/LLWU_P7_73") (pintype "passive"))
    )
    (net (code "60") (name "Net-(U2-PTC4{slash}LLWU_P8)") (class "Default")
      (node (ref "R19") (pin "1") (pinfunction "1_1") (pintype "passive"))
      (node (ref "U2") (pin "76") (pinfunction "PTC4/LLWU_P8_76") (pintype "passive"))
    )
    (net (code "61") (name "Net-(U2-PTC6{slash}LLWU_P10)") (class "Default")
      (node (ref "R21") (pin "1") (pinfunction "1_1") (pintype "passive"))
      (node (ref "U2") (pin "78") (pinfunction "PTC6/LLWU_P10_78") (pintype "passive"))
    )
    (net (code "62") (name "Net-(U2-PTC7)") (class "Default")
      (node (ref "R22") (pin "1") (pinfunction "1_1") (pintype "passive"))
      (node (ref "U2") (pin "79") (pinfunction "PTC7_79") (pintype "passive"))
    )
    (net (code "63") (name "Net-(U2-PTC8)") (class "Default")
      (node (ref "R23") (pin "1") (pinfunction "1_1") (pintype "passive"))
      (node (ref "U2") (pin "80") (pinfunction "PTC8_80") (pintype "passive"))
    )
    (net (code "64") (name "Net-(U2-PTC10)") (class "Default")
      (node (ref "R25") (pin "1") (pinfunction "1_1") (pintype "passive"))
      (node (ref "U2") (pin "82") (pinfunction "PTC10_82") (pintype "passive"))
    )
    (net (code "65") (name "Net-(U2-PTC13)") (class "Default")
      (node (ref "R29") (pin "1") (pinfunction "1_1") (pintype "passive"))
      (node (ref "U2") (pin "85") (pinfunction "PTC13_85") (pintype "passive"))
    )
    (net (code "66") (name "Net-(U2-PTC15)") (class "Default")
      (node (ref "R27") (pin "1") (pinfunction "1_1") (pintype "passive"))
      (node (ref "U2") (pin "87") (pinfunction "PTC15_87") (pintype "passive"))
    )
    (net (code "67") (name "Net-(U2-PTC16)") (class "Default")
      (node (ref "R28") (pin "1") (pinfunction "1_1") (pintype "passive"))
      (node (ref "U2") (pin "90") (pinfunction "PTC16_90") (pintype "passive"))
    )
    (net (code "68") (name "Net-(U2-PTC18)") (class "Default")
      (node (ref "R76") (pin "1") (pinfunction "1_1") (pintype "passive"))
      (node (ref "U2") (pin "92") (pinfunction "PTC18_92") (pintype "passive"))
    )
    (net (code "69") (name "Net-(U2-PTD0{slash}LLWU_P12)") (class "Default")
      (node (ref "R30") (pin "1") (pinfunction "1_1") (pintype "passive"))
      (node (ref "U2") (pin "93") (pinfunction "PTD0/LLWU_P12_93") (pintype "passive"))
    )
    (net (code "70") (name "Net-(U2-PTD3)") (class "Default")
      (node (ref "R33") (pin "1") (pinfunction "1_1") (pintype "passive"))
      (node (ref "U2") (pin "96") (pinfunction "PTD3_96") (pintype "passive"))
    )
    (net (code "71") (name "Net-(U2-PTD4{slash}LLWU_P14)") (class "Default")
      (node (ref "R35") (pin "1") (pinfunction "1_1") (pintype "passive"))
      (node (ref "U2") (pin "97") (pinfunction "PTD4/LLWU_P14_97") (pintype "passive"))
    )
    (net (code "72") (name "Net-(U2-PTD7)") (class "Default")
      (node (ref "R38") (pin "1") (pinfunction "1_1") (pintype "passive"))
      (node (ref "U2") (pin "100") (pinfunction "PTD7_100") (pintype "passive"))
    )
    (net (code "73") (name "VDD_IMCU") (class "Default")
      (node (ref "C30") (pin "1") (pinfunction "1_1") (pintype "passive"))
      (node (ref "C31") (pin "2") (pinfunction "2_2") (pintype "passive"))
      (node (ref "C32") (pin "2") (pinfunction "2_2") (pintype "passive"))
      (node (ref "C33") (pin "2") (pinfunction "2_2") (pintype "passive"))
      (node (ref "C34") (pin "1") (pinfunction "1_1") (pintype "passive"))
      (node (ref "C35") (pin "2") (pinfunction "2_2") (pintype "passive"))
      (node (ref "C36") (pin "2") (pinfunction "2_2") (pintype "passive"))
      (node (ref "C37") (pin "2") (pinfunction "2_2") (pintype "passive"))
      (node (ref "C38") (pin "2") (pinfunction "2_2") (pintype "passive"))
      (node (ref "J4") (pin "1") (pinfunction "1_1") (pintype "passive"))
      (node (ref "R10") (pin "2") (pinfunction "2_2") (pintype "passive"))
      (node (ref "R32") (pin "2") (pinfunction "2_2") (pintype "passive"))
      (node (ref "R34") (pin "2") (pinfunction "2_2") (pintype "passive"))
      (node (ref "R37") (pin "2") (pinfunction "2_2") (pintype "passive"))
      (node (ref "R39") (pin "2") (pinfunction "2_2") (pintype "passive"))
      (node (ref "R40") (pin "2") (pinfunction "2_2") (pintype "passive"))
      (node (ref "R41") (pin "2") (pinfunction "2_2") (pintype "passive"))
      (node (ref "R6") (pin "2") (pinfunction "2_2") (pintype "passive"))
      (node (ref "TP20") (pin "1") (pinfunction "1_1") (pintype "passive"))
      (node (ref "U2") (pin "22") (pinfunction "VDDA_22") (pintype "passive"))
      (node (ref "U2") (pin "23") (pinfunction "VREFH_23") (pintype "passive"))
      (node (ref "U2") (pin "30") (pinfunction "VBAT_30") (pintype "passive"))
      (node (ref "U2") (pin "40") (pinfunction "VDD_40") (pintype "passive"))
      (node (ref "U2") (pin "48") (pinfunction "VDD_48") (pintype "passive"))
      (node (ref "U2") (pin "61") (pinfunction "VDD_61") (pintype "passive"))
      (node (ref "U2") (pin "62") (pinfunction "PTB16_62") (pintype "passive"))
      (node (ref "U2") (pin "75") (pinfunction "VDD_75") (pintype "passive"))
      (node (ref "U2") (pin "8") (pinfunction "VDD_8") (pintype "passive"))
      (node (ref "U2") (pin "89") (pinfunction "VDD_89") (pintype "passive"))
      (node (ref "U8") (pin "4") (pinfunction "EN_4") (pintype "passive"))
      (node (ref "U8") (pin "6") (pinfunction "VCC_6") (pintype "power_in"))
    )
    (net (code "74") (name "VDD_IMCU_3V") (class "Default")
      (node (ref "R11") (pin "2") (pinfunction "2_2") (pintype "passive"))
      (node (ref "SB19") (pin "2") (pinfunction "1_2") (pintype "passive"))
    )
    (net (code "75") (name "unconnected-(J4-Pad7)") (class "Default")
      (node (ref "J4") (pin "7") (pinfunction "7_7") (pintype "passive+no_connect"))
    )
    (net (code "76") (name "unconnected-(J4-Pad8)") (class "Default")
      (node (ref "J4") (pin "8") (pinfunction "8_8") (pintype "passive"))
    )
    (net (code "77") (name "unconnected-(J4-Pad9)") (class "Default")
      (node (ref "J4") (pin "9") (pinfunction "9_9") (pintype "passive+no_connect"))
    )
    (net (code "78") (name "unconnected-(U2-ADC0_DM0{slash}ADC1_DM3-Pad19)") (class "Default")
      (node (ref "U2") (pin "19") (pinfunction "ADC0_DM0/ADC1_DM3_19") (pintype "passive+no_connect"))
    )
    (net (code "79") (name "unconnected-(U2-ADC0_DM1-Pad15)") (class "Default")
      (node (ref "U2") (pin "15") (pinfunction "ADC0_DM1_15") (pintype "passive+no_connect"))
    )
    (net (code "80") (name "unconnected-(U2-ADC0_DP0{slash}ADC1_DP3-Pad18)") (class "Default")
      (node (ref "U2") (pin "18") (pinfunction "ADC0_DP0/ADC1_DP3_18") (pintype "passive+no_connect"))
    )
    (net (code "81") (name "unconnected-(U2-ADC0_DP1-Pad14)") (class "Default")
      (node (ref "U2") (pin "14") (pinfunction "ADC0_DP1_14") (pintype "passive+no_connect"))
    )
    (net (code "82") (name "unconnected-(U2-ADC1_DM0{slash}ADC0_DM3-Pad21)") (class "Default")
      (node (ref "U2") (pin "21") (pinfunction "ADC1_DM0/ADC0_DM3_21") (pintype "passive+no_connect"))
    )
    (net (code "83") (name "unconnected-(U2-ADC1_DM1{slash}ADC0_DM2-Pad17)") (class "Default")
      (node (ref "U2") (pin "17") (pinfunction "ADC1_DM1/ADC0_DM2_17") (pintype "passive+no_connect"))
    )
    (net (code "84") (name "unconnected-(U2-ADC1_DP0{slash}ADC0_DP3-Pad20)") (class "Default")
      (node (ref "U2") (pin "20") (pinfunction "ADC1_DP0/ADC0_DP3_20") (pintype "passive+no_connect"))
    )
    (net (code "85") (name "unconnected-(U2-ADC1_DP1{slash}ADC0_DP2-Pad16)") (class "Default")
      (node (ref "U2") (pin "16") (pinfunction "ADC1_DP1/ADC0_DP2_16") (pintype "passive+no_connect"))
    )
    (net (code "86") (name "unconnected-(U2-DAC0_OUT{slash}CMP1_IN3{slash}ADC0_SE23-Pad27)") (class "Default")
      (node (ref "U2") (pin "27") (pinfunction "DAC0_OUT/CMP1_IN3/ADC0_SE23_27") (pintype "passive+no_connect"))
    )
    (net (code "87") (name "unconnected-(U2-EXTAL32-Pad29)") (class "Default")
      (node (ref "U2") (pin "29") (pinfunction "EXTAL32_29") (pintype "passive+no_connect"))
    )
    (net (code "88") (name "unconnected-(U2-NC-Pad13)") (class "Default")
      (node (ref "U2") (pin "13") (pinfunction "NC_13") (pintype "passive+no_connect"))
    )
    (net (code "89") (name "unconnected-(U2-PTA1-Pad35)") (class "Default")
      (node (ref "U2") (pin "35") (pinfunction "PTA1_35") (pintype "passive+no_connect"))
    )
    (net (code "90") (name "unconnected-(U2-PTA4{slash}LLWU_P3-Pad38)") (class "Default")
      (node (ref "U2") (pin "38") (pinfunction "PTA4/LLWU_P3_38") (pintype "passive+no_connect"))
    )
    (net (code "91") (name "unconnected-(U2-PTA5-Pad39)") (class "Default")
      (node (ref "U2") (pin "39") (pinfunction "PTA5_39") (pintype "passive+no_connect"))
    )
    (net (code "92") (name "unconnected-(U2-PTA12-Pad42)") (class "Default")
      (node (ref "U2") (pin "42") (pinfunction "PTA12_42") (pintype "passive+no_connect"))
    )
    (net (code "93") (name "unconnected-(U2-PTA13{slash}LLWU_P4-Pad43)") (class "Default")
      (node (ref "U2") (pin "43") (pinfunction "PTA13/LLWU_P4_43") (pintype "passive+no_connect"))
    )
    (net (code "94") (name "unconnected-(U2-PTA14-Pad44)") (class "Default")
      (node (ref "U2") (pin "44") (pinfunction "PTA14_44") (pintype "passive+no_connect"))
    )
    (net (code "95") (name "unconnected-(U2-PTA15-Pad45)") (class "Default")
      (node (ref "U2") (pin "45") (pinfunction "PTA15_45") (pintype "passive+no_connect"))
    )
    (net (code "96") (name "unconnected-(U2-PTA16-Pad46)") (class "Default")
      (node (ref "U2") (pin "46") (pinfunction "PTA16_46") (pintype "passive+no_connect"))
    )
    (net (code "97") (name "unconnected-(U2-PTA17-Pad47)") (class "Default")
      (node (ref "U2") (pin "47") (pinfunction "PTA17_47") (pintype "passive+no_connect"))
    )
    (net (code "98") (name "unconnected-(U2-PTA18-Pad50)") (class "Default")
      (node (ref "U2") (pin "50") (pinfunction "PTA18_50") (pintype "passive+no_connect"))
    )
    (net (code "99") (name "unconnected-(U2-PTB1-Pad54)") (class "Default")
      (node (ref "U2") (pin "54") (pinfunction "PTB1_54") (pintype "passive+no_connect"))
    )
    (net (code "100") (name "unconnected-(U2-PTB2-Pad55)") (class "Default")
      (node (ref "U2") (pin "55") (pinfunction "PTB2_55") (pintype "passive+no_connect"))
    )
    (net (code "101") (name "unconnected-(U2-PTB3-Pad56)") (class "Default")
      (node (ref "U2") (pin "56") (pinfunction "PTB3_56") (pintype "passive+no_connect"))
    )
    (net (code "102") (name "unconnected-(U2-PTB21-Pad67)") (class "Default")
      (node (ref "U2") (pin "67") (pinfunction "PTB21_67") (pintype "passive+no_connect"))
    )
    (net (code "103") (name "unconnected-(U2-PTB22-Pad68)") (class "Default")
      (node (ref "U2") (pin "68") (pinfunction "PTB22_68") (pintype "passive+no_connect"))
    )
    (net (code "104") (name "unconnected-(U2-PTB23-Pad69)") (class "Default")
      (node (ref "U2") (pin "69") (pinfunction "PTB23_69") (pintype "passive+no_connect"))
    )
    (net (code "105") (name "unconnected-(U2-PTC0-Pad70)") (class "Default")
      (node (ref "U2") (pin "70") (pinfunction "PTC0_70") (pintype "passive+no_connect"))
    )
    (net (code "106") (name "unconnected-(U2-PTC2-Pad72)") (class "Default")
      (node (ref "U2") (pin "72") (pinfunction "PTC2_72") (pintype "passive+no_connect"))
    )
    (net (code "107") (name "unconnected-(U2-PTC5{slash}LLWU_P9-Pad77)") (class "Default")
      (node (ref "U2") (pin "77") (pinfunction "PTC5/LLWU_P9_77") (pintype "passive"))
    )
    (net (code "108") (name "unconnected-(U2-PTC9-Pad81)") (class "Default")
      (node (ref "U2") (pin "81") (pinfunction "PTC9_81") (pintype "passive"))
    )
    (net (code "109") (name "unconnected-(U2-PTC14-Pad86)") (class "Default")
      (node (ref "U2") (pin "86") (pinfunction "PTC14_86") (pintype "passive+no_connect"))
    )
    (net (code "110") (name "unconnected-(U2-PTC17-Pad91)") (class "Default")
      (node (ref "U2") (pin "91") (pinfunction "PTC17_91") (pintype "passive"))
    )
    (net (code "111") (name "unconnected-(U2-PTE0{slash}CLKOUT32K-Pad1)") (class "Default")
      (node (ref "U2") (pin "1") (pinfunction "PTE0/CLKOUT32K_1") (pintype "passive+no_connect"))
    )
    (net (code "112") (name "unconnected-(U2-PTE4{slash}LLWU_P2-Pad5)") (class "Default")
      (node (ref "U2") (pin "5") (pinfunction "PTE4/LLWU_P2_5") (pintype "passive+no_connect"))
    )
    (net (code "113") (name "unconnected-(U2-PTE5-Pad6)") (class "Default")
      (node (ref "U2") (pin "6") (pinfunction "PTE5_6") (pintype "passive+no_connect"))
    )
    (net (code "114") (name "unconnected-(U2-PTE6-Pad7)") (class "Default")
      (node (ref "U2") (pin "7") (pinfunction "PTE6_7") (pintype "passive+no_connect"))
    )
    (net (code "115") (name "unconnected-(U2-PTE24-Pad31)") (class "Default")
      (node (ref "U2") (pin "31") (pinfunction "PTE24_31") (pintype "passive+no_connect"))
    )
    (net (code "116") (name "unconnected-(U2-PTE25-Pad32)") (class "Default")
      (node (ref "U2") (pin "32") (pinfunction "PTE25_32") (pintype "passive+no_connect"))
    )
    (net (code "117") (name "unconnected-(U2-PTE26{slash}CLKOUT32K-Pad33)") (class "Default")
      (node (ref "U2") (pin "33") (pinfunction "PTE26/CLKOUT32K_33") (pintype "passive+no_connect"))
    )
    (net (code "118") (name "unconnected-(U2-VREF_OUT{slash}CMP1_IN5{slash}CMP0_IN5{slash}ADC1_SE18-Pad26)") (class "Default")
      (node (ref "U2") (pin "26") (pinfunction "VREF_OUT/CMP1_IN5/CMP0_IN5/ADC1_SE18_26") (pintype "passive+no_connect"))
    )
    (net (code "119") (name "unconnected-(U2-XTAL32-Pad28)") (class "Default")
      (node (ref "U2") (pin "28") (pinfunction "XTAL32_28") (pintype "passive+no_connect"))
    )
    (net (code "120") (name "unconnected-(U8-NC-Pad5)") (class "Default")
      (node (ref "U8") (pin "5") (pinfunction "NC_5") (pintype "passive+no_connect"))
    )
    (net (code "121") (name "unconnected-(U8-NC-Pad11)") (class "Default")
      (node (ref "U8") (pin "11") (pinfunction "NC_11") (pintype "passive+no_connect"))
    )
    (net (code "122") (name "unconnected-(U8-S2-Pad9)") (class "Default")
      (node (ref "U8") (pin "9") (pinfunction "S2_9") (pintype "passive"))
    )
  )
)
